# prototype.net
KiCad netlist of a schematic drawn in EAGLE
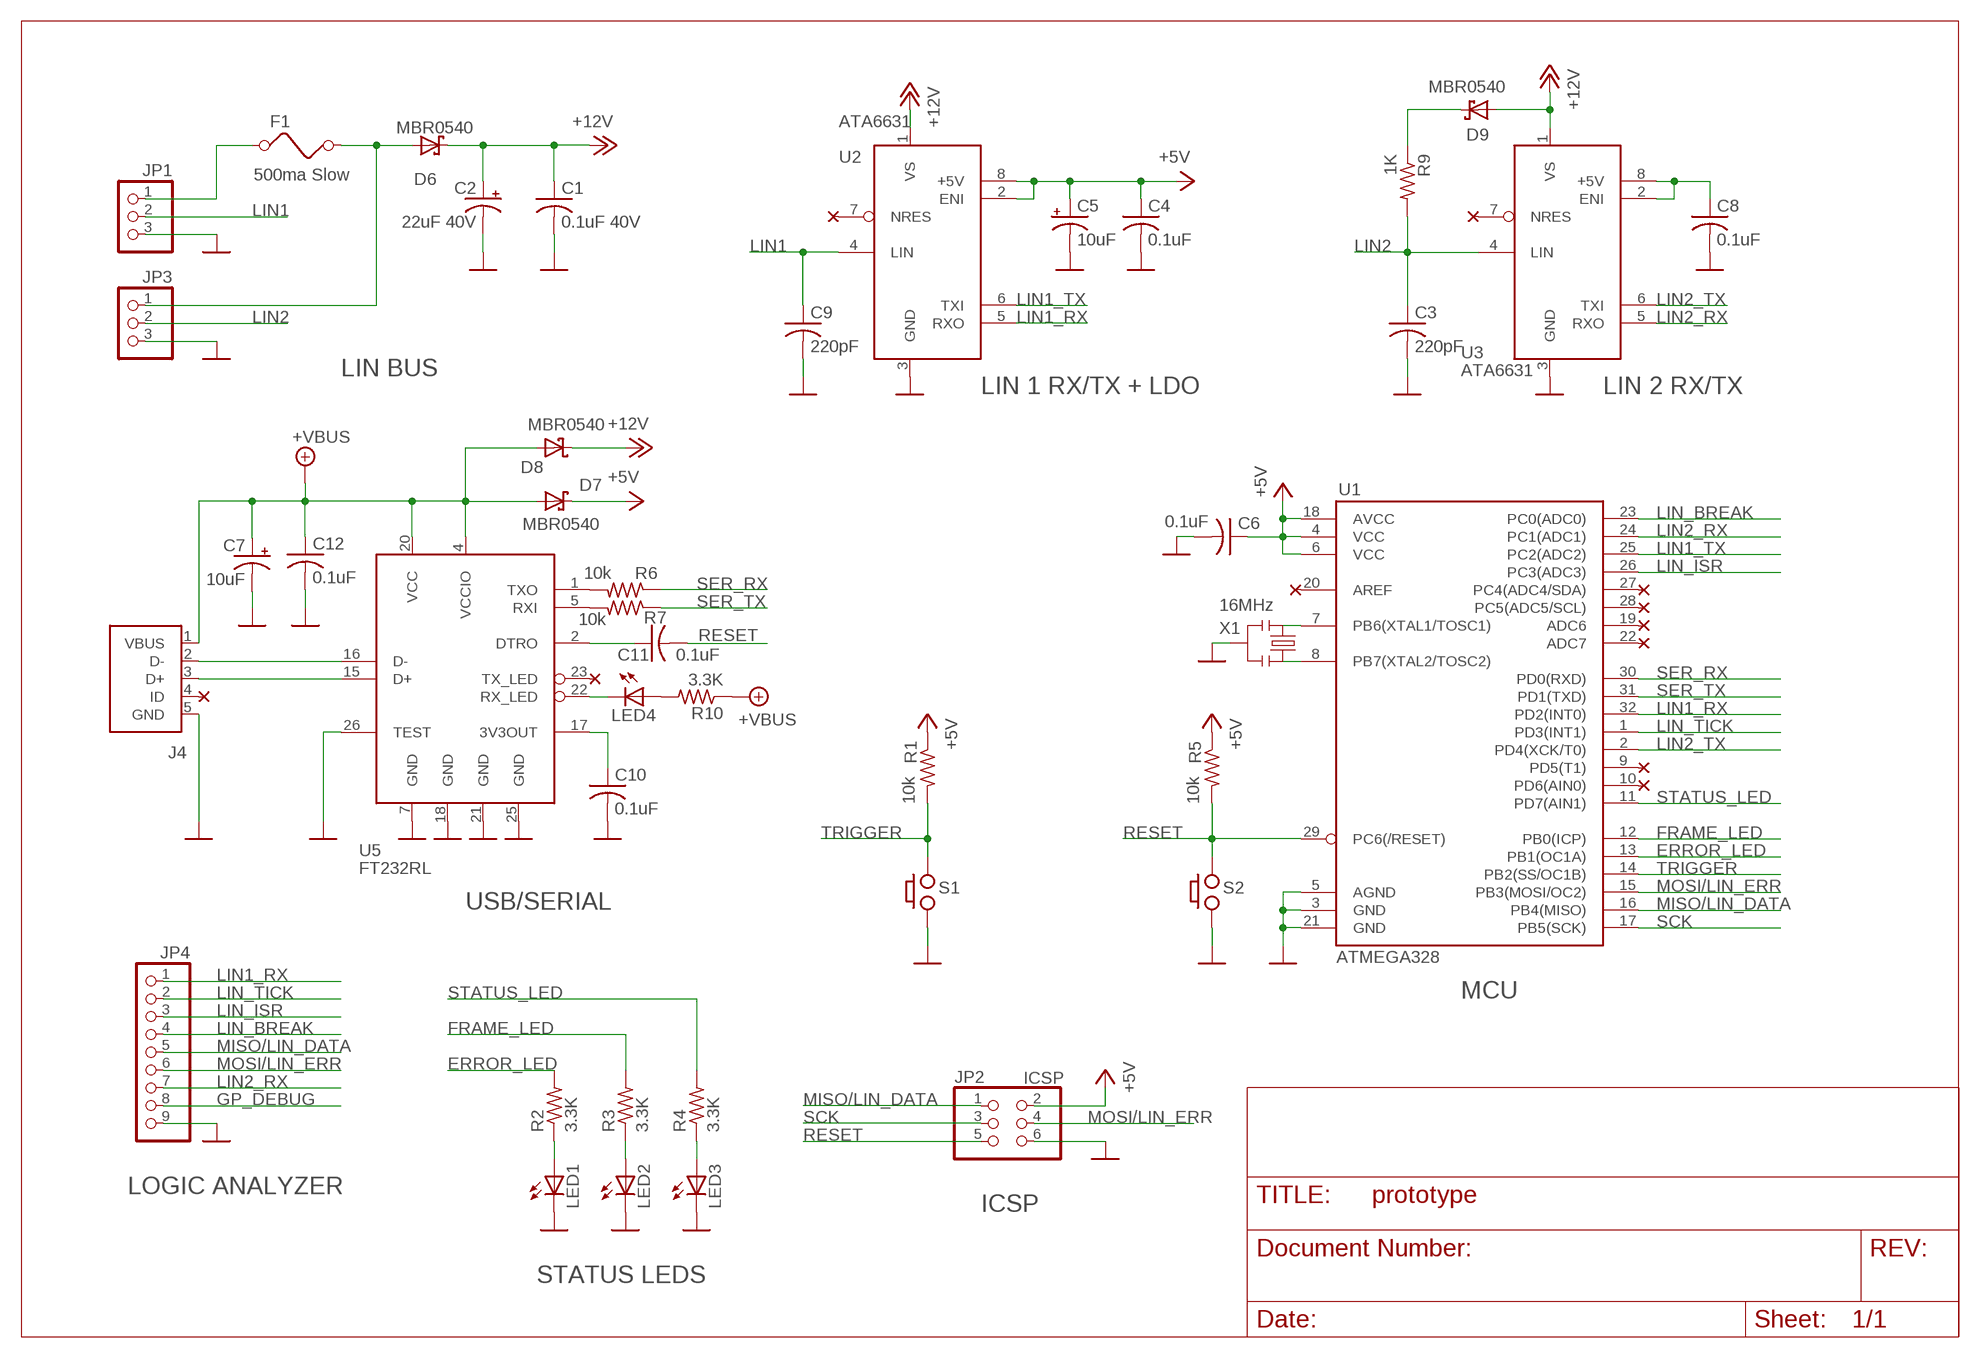
[diagram p0: schematic, sheet 1]

(export (version "E")
  (design (tool "Eeschema 10.0.6"))
  (components
    (comp (ref "C1")
      (value "0.1uF 40V")
      (footprint "eagle-import:C0805")
      (libsource (lib "eagle-import") (part "C-USC0805"))
    )
    (comp (ref "C2")
      (value "22uF 40V")
      (footprint "eagle-import:UD-6,3X5,8_NICHICON")
      (libsource (lib "eagle-import") (part "CPOL-USUD-6,3X5,8"))
    )
    (comp (ref "C3")
      (value "220pF")
      (footprint "eagle-import:C0805")
      (libsource (lib "eagle-import") (part "C-USC0805"))
    )
    (comp (ref "C4")
      (value "0.1uF")
      (footprint "eagle-import:C0805")
      (libsource (lib "eagle-import") (part "C-USC0805"))
    )
    (comp (ref "C5")
      (value "10uF")
      (footprint "eagle-import:A_3216-18R")
      (libsource (lib "eagle-import") (part "CPOL-USA/3216-18R"))
    )
    (comp (ref "C6")
      (value "0.1uF")
      (footprint "eagle-import:C0805")
      (libsource (lib "eagle-import") (part "C-USC0805"))
    )
    (comp (ref "C7")
      (value "10uF")
      (footprint "eagle-import:A_3216-18R")
      (libsource (lib "eagle-import") (part "CPOL-USA/3216-18R"))
    )
    (comp (ref "C8")
      (value "0.1uF")
      (footprint "eagle-import:C0805")
      (libsource (lib "eagle-import") (part "C-USC0805"))
    )
    (comp (ref "C9")
      (value "220pF")
      (footprint "eagle-import:C0805")
      (libsource (lib "eagle-import") (part "C-USC0805"))
    )
    (comp (ref "C10")
      (value "0.1uF")
      (footprint "eagle-import:C0805")
      (libsource (lib "eagle-import") (part "C-USC0805"))
    )
    (comp (ref "C11")
      (value "0.1uF")
      (footprint "eagle-import:C0805")
      (libsource (lib "eagle-import") (part "C-USC0805"))
    )
    (comp (ref "C12")
      (value "0.1uF")
      (footprint "eagle-import:C0805")
      (libsource (lib "eagle-import") (part "C-USC0805"))
    )
    (comp (ref "D6")
      (value "MBR0540")
      (footprint "eagle-import:SOD123FL")
      (libsource (lib "eagle-import") (part "SMF5.0AT1"))
    )
    (comp (ref "D7")
      (value "MBR0540")
      (footprint "eagle-import:SOD123FL")
      (libsource (lib "eagle-import") (part "SMF5.0AT1"))
    )
    (comp (ref "D8")
      (value "MBR0540")
      (footprint "eagle-import:SOD123FL")
      (libsource (lib "eagle-import") (part "SMF5.0AT1"))
    )
    (comp (ref "D9")
      (value "MBR0540")
      (footprint "eagle-import:SOD123FL")
      (libsource (lib "eagle-import") (part "SMF5.0AT1"))
    )
    (comp (ref "F1")
      (value "500ma Slow")
      (footprint "eagle-import:1206")
      (libsource (lib "eagle-import") (part "FUSE"))
    )
    (comp (ref "J4")
      (value "USBSMD")
      (footprint "eagle-import:USB-MINIB")
      (libsource (lib "eagle-import") (part "USBSMD"))
    )
    (comp (ref "JP1")
      (value "PINHD-1X3")
      (footprint "eagle-import:1X03")
      (libsource (lib "eagle-import") (part "PINHD-1X3"))
    )
    (comp (ref "JP2")
      (value "ICSP")
      (footprint "eagle-import:2X03")
      (libsource (lib "eagle-import") (part "PINHD-2X3"))
    )
    (comp (ref "JP3")
      (value "PINHD-1X3")
      (footprint "eagle-import:1X03")
      (libsource (lib "eagle-import") (part "PINHD-1X3"))
    )
    (comp (ref "JP4")
      (value "PINHD-1X9")
      (footprint "eagle-import:1X09")
      (libsource (lib "eagle-import") (part "PINHD-1X9"))
    )
    (comp (ref "LED1")
      (value "LED")
      (footprint "eagle-import:1206-LED")
      (libsource (lib "eagle-import") (part "LED"))
    )
    (comp (ref "LED2")
      (value "LED")
      (footprint "eagle-import:1206-LED")
      (libsource (lib "eagle-import") (part "LED"))
    )
    (comp (ref "LED3")
      (value "LED")
      (footprint "eagle-import:1206-LED")
      (libsource (lib "eagle-import") (part "LED"))
    )
    (comp (ref "LED4")
      (value "LED")
      (footprint "eagle-import:1206-LED")
      (libsource (lib "eagle-import") (part "LED"))
    )
    (comp (ref "R1")
      (value "10k")
      (footprint "eagle-import:R0805")
      (libsource (lib "eagle-import") (part "R-US_R0805"))
    )
    (comp (ref "R2")
      (value "3.3K")
      (footprint "eagle-import:R0805")
      (libsource (lib "eagle-import") (part "R-US_R0805"))
    )
    (comp (ref "R3")
      (value "3.3K")
      (footprint "eagle-import:R0805")
      (libsource (lib "eagle-import") (part "R-US_R0805"))
    )
    (comp (ref "R4")
      (value "3.3K")
      (footprint "eagle-import:R0805")
      (libsource (lib "eagle-import") (part "R-US_R0805"))
    )
    (comp (ref "R5")
      (value "10k")
      (footprint "eagle-import:R0805")
      (libsource (lib "eagle-import") (part "R-US_R0805"))
    )
    (comp (ref "R6")
      (value "10k")
      (footprint "eagle-import:R0805")
      (libsource (lib "eagle-import") (part "R-US_R0805"))
    )
    (comp (ref "R7")
      (value "10k")
      (footprint "eagle-import:R0805")
      (libsource (lib "eagle-import") (part "R-US_R0805"))
    )
    (comp (ref "R9")
      (value "1K")
      (footprint "eagle-import:R0805")
      (libsource (lib "eagle-import") (part "R-US_R0805"))
    )
    (comp (ref "R10")
      (value "3.3K")
      (footprint "eagle-import:R0805")
      (libsource (lib "eagle-import") (part "R-US_R0805"))
    )
    (comp (ref "S1")
      (value "PUSH_BUTTON")
      (footprint "eagle-import:DUMMY-2")
      (libsource (lib "eagle-import") (part "PUSH_BUTTON"))
    )
    (comp (ref "S2")
      (value "PUSH_BUTTON")
      (footprint "eagle-import:DUMMY-2")
      (libsource (lib "eagle-import") (part "PUSH_BUTTON"))
    )
    (comp (ref "U1")
      (value "ATMEGA328")
      (footprint "eagle-import:TQFP32-08")
      (libsource (lib "eagle-import") (part "ATMEGA328"))
    )
    (comp (ref "U2")
      (value "ATA6631")
      (footprint "eagle-import:SO-08")
      (libsource (lib "eagle-import") (part "ATA6631"))
    )
    (comp (ref "U3")
      (value "ATA6631")
      (footprint "eagle-import:SO-08")
      (libsource (lib "eagle-import") (part "ATA6631"))
    )
    (comp (ref "U5")
      (value "FT232RL")
      (footprint "eagle-import:SSOP28DB")
      (libsource (lib "eagle-import") (part "FT232RL"))
    )
    (comp (ref "X1")
      (value "16MHz")
      (footprint "eagle-import:RESONATOR-SMD")
      (libsource (lib "eagle-import") (part "RESONATORSMD"))
    )
  )
  (nets
    (net (code "1") (name "+5V") (class "Default")
      (node (ref "C4") (pin "1") (pinfunction "1_1") (pintype "passive"))
      (node (ref "C5") (pin "+") (pinfunction "+_+") (pintype "passive"))
      (node (ref "C6") (pin "1") (pinfunction "1_1") (pintype "passive"))
      (node (ref "D7") (pin "C") (pinfunction "C_C") (pintype "passive"))
      (node (ref "JP2") (pin "2") (pinfunction "2_2") (pintype "passive"))
      (node (ref "R1") (pin "1") (pinfunction "1_1") (pintype "passive"))
      (node (ref "R5") (pin "1") (pinfunction "1_1") (pintype "passive"))
      (node (ref "U1") (pin "18") (pinfunction "AVCC_18") (pintype "power_in"))
      (node (ref "U1") (pin "4") (pinfunction "VCC_4") (pintype "power_in"))
      (node (ref "U1") (pin "6") (pinfunction "VCC_6") (pintype "power_in"))
      (node (ref "U2") (pin "2") (pinfunction "ENI_2") (pintype "input"))
      (node (ref "U2") (pin "8") (pinfunction "+5V_8") (pintype "power_in"))
    )
    (net (code "2") (name "+12V") (class "Default")
      (node (ref "C1") (pin "1") (pinfunction "1_1") (pintype "passive"))
      (node (ref "C2") (pin "+") (pinfunction "+_+") (pintype "passive"))
      (node (ref "D6") (pin "C") (pinfunction "C_C") (pintype "passive"))
      (node (ref "D8") (pin "C") (pinfunction "C_C") (pintype "passive"))
      (node (ref "D9") (pin "A") (pinfunction "A_A") (pintype "passive"))
      (node (ref "U2") (pin "1") (pinfunction "VS_1") (pintype "power_in"))
      (node (ref "U3") (pin "1") (pinfunction "VS_1") (pintype "power_in"))
    )
    (net (code "3") (name "+VBUS") (class "Default")
      (node (ref "C12") (pin "1") (pinfunction "1_1") (pintype "passive"))
      (node (ref "C7") (pin "+") (pinfunction "+_+") (pintype "passive"))
      (node (ref "D7") (pin "A") (pinfunction "A_A") (pintype "passive"))
      (node (ref "D8") (pin "A") (pinfunction "A_A") (pintype "passive"))
      (node (ref "J4") (pin "1") (pinfunction "VBUS_1") (pintype "bidirectional"))
      (node (ref "R10") (pin "1") (pinfunction "1_1") (pintype "passive"))
      (node (ref "U5") (pin "20") (pinfunction "VCC_20") (pintype "power_in"))
      (node (ref "U5") (pin "4") (pinfunction "VCCIO_4") (pintype "power_in"))
    )
    (net (code "4") (name "/AREF") (class "Default")
      (node (ref "U1") (pin "20") (pinfunction "AREF_20") (pintype "power_in"))
    )
    (net (code "5") (name "/ERROR_LED") (class "Default")
      (node (ref "R2") (pin "2") (pinfunction "2_2") (pintype "passive"))
      (node (ref "U1") (pin "13") (pinfunction "PB1(OC1A)_13") (pintype "bidirectional"))
    )
    (net (code "6") (name "/FRAME_LED") (class "Default")
      (node (ref "R3") (pin "2") (pinfunction "2_2") (pintype "passive"))
      (node (ref "U1") (pin "12") (pinfunction "PB0(ICP)_12") (pintype "bidirectional"))
    )
    (net (code "7") (name "/GP_DEBUG") (class "Default")
      (node (ref "JP4") (pin "8") (pinfunction "8_8") (pintype "passive"))
    )
    (net (code "8") (name "/LIN1") (class "Default")
      (node (ref "C9") (pin "1") (pinfunction "1_1") (pintype "passive"))
      (node (ref "JP1") (pin "2") (pinfunction "2_2") (pintype "passive"))
      (node (ref "U2") (pin "4") (pinfunction "LIN_4") (pintype "bidirectional"))
    )
    (net (code "9") (name "/LIN1_RX") (class "Default")
      (node (ref "JP4") (pin "1") (pinfunction "1_1") (pintype "passive"))
      (node (ref "U1") (pin "32") (pinfunction "PD2(INT0)_32") (pintype "bidirectional"))
      (node (ref "U2") (pin "5") (pinfunction "RXO_5") (pintype "output"))
    )
    (net (code "10") (name "/LIN1_TX") (class "Default")
      (node (ref "U1") (pin "25") (pinfunction "PC2(ADC2)_25") (pintype "bidirectional"))
      (node (ref "U2") (pin "6") (pinfunction "TXI_6") (pintype "input"))
    )
    (net (code "11") (name "/LIN2") (class "Default")
      (node (ref "C3") (pin "1") (pinfunction "1_1") (pintype "passive"))
      (node (ref "JP3") (pin "2") (pinfunction "2_2") (pintype "passive"))
      (node (ref "R9") (pin "2") (pinfunction "2_2") (pintype "passive"))
      (node (ref "U3") (pin "4") (pinfunction "LIN_4") (pintype "bidirectional"))
    )
    (net (code "12") (name "/LIN2_RX") (class "Default")
      (node (ref "JP4") (pin "7") (pinfunction "7_7") (pintype "passive"))
      (node (ref "U1") (pin "24") (pinfunction "PC1(ADC1)_24") (pintype "bidirectional"))
      (node (ref "U3") (pin "5") (pinfunction "RXO_5") (pintype "output"))
    )
    (net (code "13") (name "/LIN2_TX") (class "Default")
      (node (ref "U1") (pin "2") (pinfunction "PD4(XCK/T0)_2") (pintype "bidirectional"))
      (node (ref "U3") (pin "6") (pinfunction "TXI_6") (pintype "input"))
    )
    (net (code "14") (name "/LIN_BREAK") (class "Default")
      (node (ref "JP4") (pin "4") (pinfunction "4_4") (pintype "passive"))
      (node (ref "U1") (pin "23") (pinfunction "PC0(ADC0)_23") (pintype "bidirectional"))
    )
    (net (code "15") (name "/LIN_ISR") (class "Default")
      (node (ref "JP4") (pin "3") (pinfunction "3_3") (pintype "passive"))
      (node (ref "U1") (pin "26") (pinfunction "PC3(ADC3)_26") (pintype "bidirectional"))
    )
    (net (code "16") (name "/LIN_TICK") (class "Default")
      (node (ref "JP4") (pin "2") (pinfunction "2_2") (pintype "passive"))
      (node (ref "U1") (pin "1") (pinfunction "PD3(INT1)_1") (pintype "bidirectional"))
    )
    (net (code "17") (name "/MISO{slash}LIN_DATA") (class "Default")
      (node (ref "JP2") (pin "1") (pinfunction "1_1") (pintype "passive"))
      (node (ref "JP4") (pin "5") (pinfunction "5_5") (pintype "passive"))
      (node (ref "U1") (pin "16") (pinfunction "PB4(MISO)_16") (pintype "bidirectional"))
    )
    (net (code "18") (name "/MOSI{slash}LIN_ERR") (class "Default")
      (node (ref "JP2") (pin "4") (pinfunction "4_4") (pintype "passive"))
      (node (ref "JP4") (pin "6") (pinfunction "6_6") (pintype "passive"))
      (node (ref "U1") (pin "15") (pinfunction "PB3(MOSI/OC2)_15") (pintype "bidirectional"))
    )
    (net (code "19") (name "/RESET") (class "Default")
      (node (ref "C11") (pin "2") (pinfunction "2_2") (pintype "passive"))
      (node (ref "JP2") (pin "5") (pinfunction "5_5") (pintype "passive"))
      (node (ref "R5") (pin "2") (pinfunction "2_2") (pintype "passive"))
      (node (ref "S2") (pin "P$1") (pinfunction "P$3_P$1") (pintype "passive"))
      (node (ref "U1") (pin "29") (pinfunction "PC6(/RESET)_29") (pintype "bidirectional"))
    )
    (net (code "20") (name "/SCK") (class "Default")
      (node (ref "JP2") (pin "3") (pinfunction "3_3") (pintype "passive"))
      (node (ref "U1") (pin "17") (pinfunction "PB5(SCK)_17") (pintype "bidirectional"))
    )
    (net (code "21") (name "/SER_RX") (class "Default")
      (node (ref "R6") (pin "1") (pinfunction "1_1") (pintype "passive"))
      (node (ref "U1") (pin "30") (pinfunction "PD0(RXD)_30") (pintype "bidirectional"))
    )
    (net (code "22") (name "/SER_TX") (class "Default")
      (node (ref "R7") (pin "1") (pinfunction "1_1") (pintype "passive"))
      (node (ref "U1") (pin "31") (pinfunction "PD1(TXD)_31") (pintype "bidirectional"))
    )
    (net (code "23") (name "/STATUS_LED") (class "Default")
      (node (ref "R4") (pin "2") (pinfunction "2_2") (pintype "passive"))
      (node (ref "U1") (pin "11") (pinfunction "PD7(AIN1)_11") (pintype "bidirectional"))
    )
    (net (code "24") (name "/TRIGGER") (class "Default")
      (node (ref "R1") (pin "2") (pinfunction "2_2") (pintype "passive"))
      (node (ref "S1") (pin "P$1") (pinfunction "P$3_P$1") (pintype "passive"))
      (node (ref "U1") (pin "14") (pinfunction "PB2(SS/OC1B)_14") (pintype "bidirectional"))
    )
    (net (code "25") (name "GND") (class "Default")
      (node (ref "C1") (pin "2") (pinfunction "2_2") (pintype "passive"))
      (node (ref "C10") (pin "2") (pinfunction "2_2") (pintype "passive"))
      (node (ref "C12") (pin "2") (pinfunction "2_2") (pintype "passive"))
      (node (ref "C2") (pin "-") (pinfunction "-_-") (pintype "passive"))
      (node (ref "C3") (pin "2") (pinfunction "2_2") (pintype "passive"))
      (node (ref "C4") (pin "2") (pinfunction "2_2") (pintype "passive"))
      (node (ref "C5") (pin "-") (pinfunction "-_-") (pintype "passive"))
      (node (ref "C6") (pin "2") (pinfunction "2_2") (pintype "passive"))
      (node (ref "C7") (pin "-") (pinfunction "-_-") (pintype "passive"))
      (node (ref "C8") (pin "2") (pinfunction "2_2") (pintype "passive"))
      (node (ref "C9") (pin "2") (pinfunction "2_2") (pintype "passive"))
      (node (ref "J4") (pin "5") (pinfunction "GND_5") (pintype "bidirectional"))
      (node (ref "JP1") (pin "3") (pinfunction "3_3") (pintype "passive"))
      (node (ref "JP2") (pin "6") (pinfunction "6_6") (pintype "passive"))
      (node (ref "JP3") (pin "3") (pinfunction "3_3") (pintype "passive"))
      (node (ref "JP4") (pin "9") (pinfunction "9_9") (pintype "passive"))
      (node (ref "LED1") (pin "C") (pinfunction "C_C") (pintype "passive"))
      (node (ref "LED2") (pin "C") (pinfunction "C_C") (pintype "passive"))
      (node (ref "LED3") (pin "C") (pinfunction "C_C") (pintype "passive"))
      (node (ref "S1") (pin "P$2") (pinfunction "P$4_P$2") (pintype "passive"))
      (node (ref "S2") (pin "P$2") (pinfunction "P$4_P$2") (pintype "passive"))
      (node (ref "U1") (pin "21") (pinfunction "GND_21") (pintype "power_in"))
      (node (ref "U1") (pin "3") (pinfunction "GND_3") (pintype "power_in"))
      (node (ref "U1") (pin "5") (pinfunction "AGND_5") (pintype "power_in"))
      (node (ref "U2") (pin "3") (pinfunction "GND_3") (pintype "power_in"))
      (node (ref "U3") (pin "3") (pinfunction "GND_3") (pintype "power_in"))
      (node (ref "U5") (pin "18") (pinfunction "GND_18") (pintype "power_in"))
      (node (ref "U5") (pin "21") (pinfunction "GND_21") (pintype "power_in"))
      (node (ref "U5") (pin "25") (pinfunction "GND_25") (pintype "power_in"))
      (node (ref "U5") (pin "26") (pinfunction "TEST_26") (pintype "input"))
      (node (ref "U5") (pin "7") (pinfunction "GND_7") (pintype "power_in"))
      (node (ref "X1") (pin "2") (pinfunction "2_2") (pintype "passive"))
    )
    (net (code "26") (name "Net-(D6-PadA)") (class "Default")
      (node (ref "D6") (pin "A") (pinfunction "A_A") (pintype "passive"))
      (node (ref "F1") (pin "2") (pinfunction "2_2") (pintype "passive"))
      (node (ref "JP3") (pin "1") (pinfunction "1_1") (pintype "passive"))
    )
    (net (code "27") (name "Net-(D9-PadC)") (class "Default")
      (node (ref "D9") (pin "C") (pinfunction "C_C") (pintype "passive"))
      (node (ref "R9") (pin "1") (pinfunction "1_1") (pintype "passive"))
    )
    (net (code "28") (name "Net-(F1-Pad1)") (class "Default")
      (node (ref "F1") (pin "1") (pinfunction "1_1") (pintype "passive"))
      (node (ref "JP1") (pin "1") (pinfunction "1_1") (pintype "passive"))
    )
    (net (code "29") (name "Net-(J4-D+)") (class "Default")
      (node (ref "J4") (pin "3") (pinfunction "D+_3") (pintype "bidirectional"))
      (node (ref "U5") (pin "15") (pinfunction "D+_15") (pintype "passive"))
    )
    (net (code "30") (name "Net-(J4-D-)") (class "Default")
      (node (ref "J4") (pin "2") (pinfunction "D-_2") (pintype "bidirectional"))
      (node (ref "U5") (pin "16") (pinfunction "D-_16") (pintype "passive"))
    )
    (net (code "31") (name "Net-(LED1-PadA)") (class "Default")
      (node (ref "LED1") (pin "A") (pinfunction "A_A") (pintype "passive"))
      (node (ref "R2") (pin "1") (pinfunction "1_1") (pintype "passive"))
    )
    (net (code "32") (name "Net-(LED2-PadA)") (class "Default")
      (node (ref "LED2") (pin "A") (pinfunction "A_A") (pintype "passive"))
      (node (ref "R3") (pin "1") (pinfunction "1_1") (pintype "passive"))
    )
    (net (code "33") (name "Net-(LED3-PadA)") (class "Default")
      (node (ref "LED3") (pin "A") (pinfunction "A_A") (pintype "passive"))
      (node (ref "R4") (pin "1") (pinfunction "1_1") (pintype "passive"))
    )
    (net (code "34") (name "Net-(LED4-PadA)") (class "Default")
      (node (ref "LED4") (pin "A") (pinfunction "A_A") (pintype "passive"))
      (node (ref "R10") (pin "2") (pinfunction "2_2") (pintype "passive"))
    )
    (net (code "35") (name "Net-(U1-PB6(XTAL1{slash}TOSC1))") (class "Default")
      (node (ref "U1") (pin "7") (pinfunction "PB6(XTAL1/TOSC1)_7") (pintype "bidirectional"))
      (node (ref "X1") (pin "3") (pinfunction "3_3") (pintype "passive"))
    )
    (net (code "36") (name "Net-(U1-PB7(XTAL2{slash}TOSC2))") (class "Default")
      (node (ref "U1") (pin "8") (pinfunction "PB7(XTAL2/TOSC2)_8") (pintype "bidirectional"))
      (node (ref "X1") (pin "1") (pinfunction "1_1") (pintype "passive"))
    )
    (net (code "37") (name "Net-(U3-+5V)") (class "Default")
      (node (ref "C8") (pin "1") (pinfunction "1_1") (pintype "passive"))
      (node (ref "U3") (pin "2") (pinfunction "ENI_2") (pintype "input"))
      (node (ref "U3") (pin "8") (pinfunction "+5V_8") (pintype "power_in"))
    )
    (net (code "38") (name "Net-(U5-3V3OUT)") (class "Default")
      (node (ref "C10") (pin "1") (pinfunction "1_1") (pintype "passive"))
      (node (ref "U5") (pin "17") (pinfunction "3V3OUT_17") (pintype "power_in"))
    )
    (net (code "39") (name "Net-(U5-DTRO)") (class "Default")
      (node (ref "C11") (pin "1") (pinfunction "1_1") (pintype "passive"))
      (node (ref "U5") (pin "2") (pinfunction "DTRO_2") (pintype "output"))
    )
    (net (code "40") (name "Net-(U5-RXI)") (class "Default")
      (node (ref "R7") (pin "2") (pinfunction "2_2") (pintype "passive"))
      (node (ref "U5") (pin "5") (pinfunction "RXI_5") (pintype "input"))
    )
    (net (code "41") (name "Net-(U5-RX_LED)") (class "Default")
      (node (ref "LED4") (pin "C") (pinfunction "C_C") (pintype "passive"))
      (node (ref "U5") (pin "22") (pinfunction "RX_LED_22") (pintype "output"))
    )
    (net (code "42") (name "Net-(U5-TXO)") (class "Default")
      (node (ref "R6") (pin "2") (pinfunction "2_2") (pintype "passive"))
      (node (ref "U5") (pin "1") (pinfunction "TXO_1") (pintype "output"))
    )
    (net (code "43") (name "unconnected-(J4-ID-Pad4)") (class "Default")
      (node (ref "J4") (pin "4") (pinfunction "ID_4") (pintype "bidirectional"))
    )
    (net (code "44") (name "unconnected-(U1-ADC6-Pad19)") (class "Default")
      (node (ref "U1") (pin "19") (pinfunction "ADC6_19") (pintype "bidirectional"))
    )
    (net (code "45") (name "unconnected-(U1-ADC7-Pad22)") (class "Default")
      (node (ref "U1") (pin "22") (pinfunction "ADC7_22") (pintype "bidirectional"))
    )
    (net (code "46") (name "unconnected-(U1-PC4(ADC4{slash}SDA)-Pad27)") (class "Default")
      (node (ref "U1") (pin "27") (pinfunction "PC4(ADC4/SDA)_27") (pintype "bidirectional"))
    )
    (net (code "47") (name "unconnected-(U1-PC5(ADC5{slash}SCL)-Pad28)") (class "Default")
      (node (ref "U1") (pin "28") (pinfunction "PC5(ADC5/SCL)_28") (pintype "bidirectional"))
    )
    (net (code "48") (name "unconnected-(U1-PD5(T1)-Pad9)") (class "Default")
      (node (ref "U1") (pin "9") (pinfunction "PD5(T1)_9") (pintype "bidirectional"))
    )
    (net (code "49") (name "unconnected-(U1-PD6(AIN0)-Pad10)") (class "Default")
      (node (ref "U1") (pin "10") (pinfunction "PD6(AIN0)_10") (pintype "bidirectional"))
    )
    (net (code "50") (name "unconnected-(U2-NRES-Pad7)") (class "Default")
      (node (ref "U2") (pin "7") (pinfunction "NRES_7") (pintype "output"))
    )
    (net (code "51") (name "unconnected-(U3-NRES-Pad7)") (class "Default")
      (node (ref "U3") (pin "7") (pinfunction "NRES_7") (pintype "output"))
    )
    (net (code "52") (name "unconnected-(U5-TX_LED-Pad23)") (class "Default")
      (node (ref "U5") (pin "23") (pinfunction "TX_LED_23") (pintype "output"))
    )
  )
)
